# EBF6ULL_B1____AD.net
KiCad netlist of a schematic drawn in Altium Designer
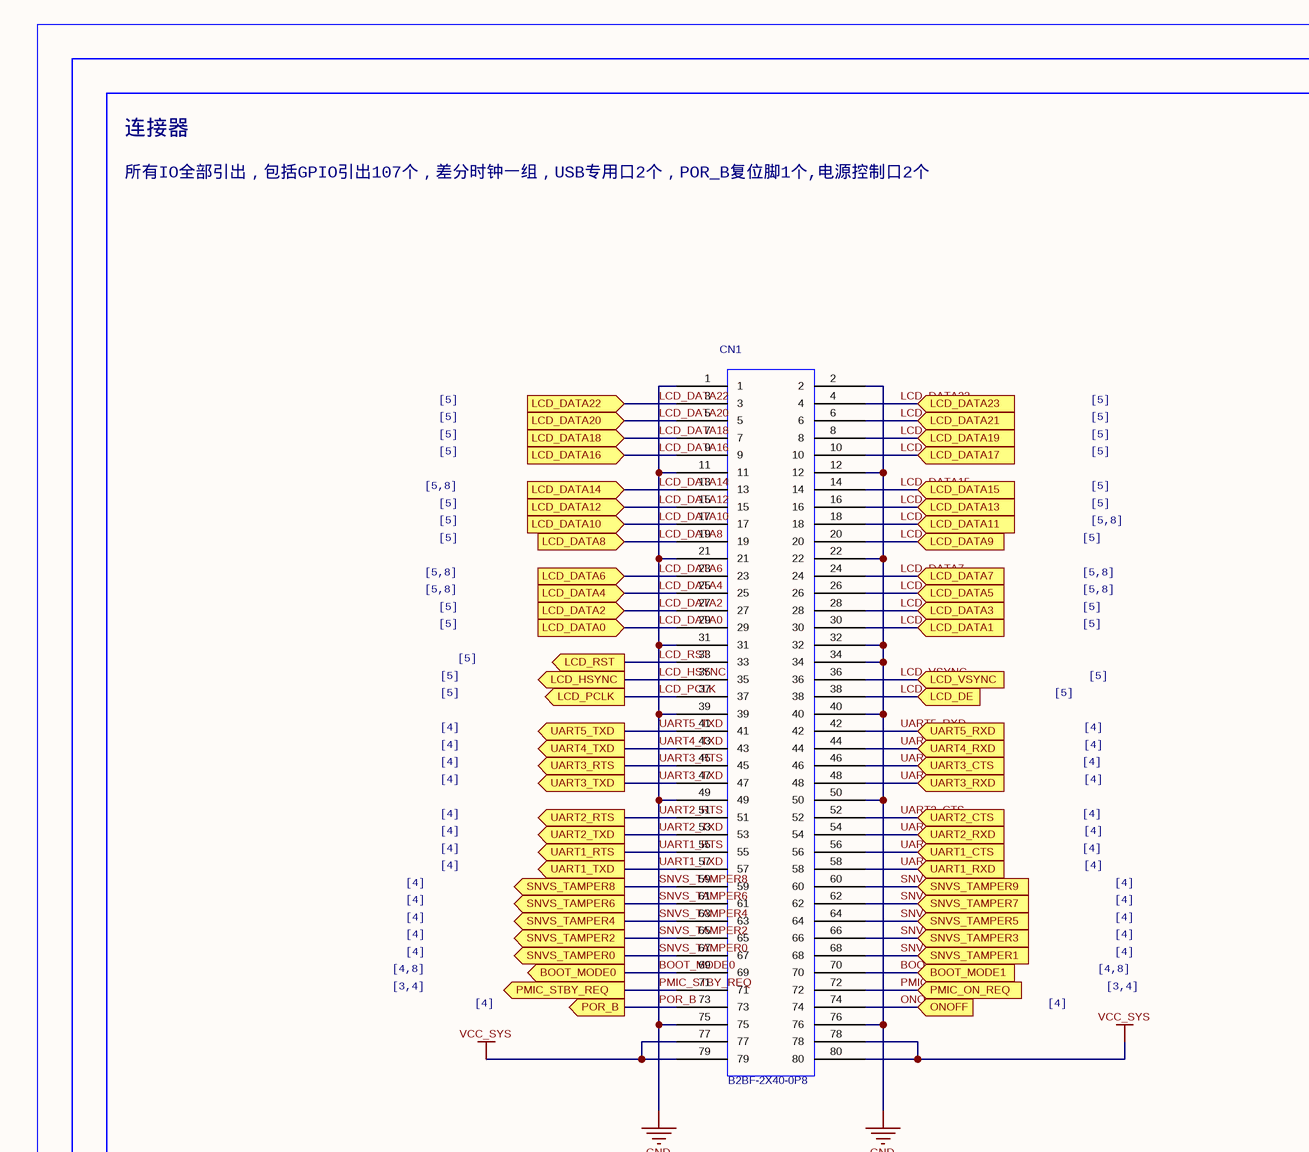
[diagram p0: 野火_EBF6ULL B1 核心板_原理图封装参考设计_AD格式.SchDoc, top left]
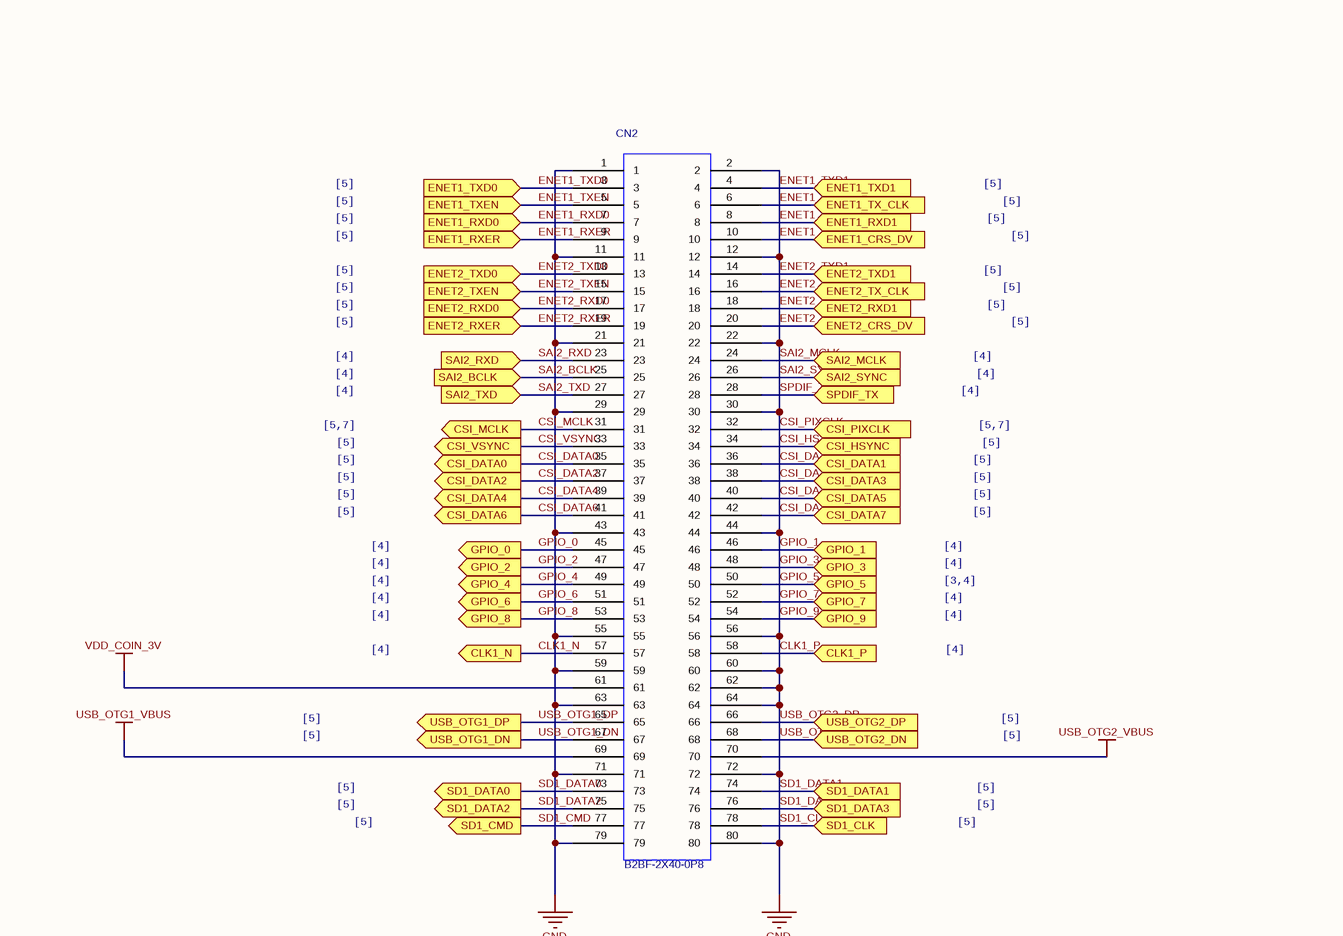
[diagram p1: 野火_EBF6ULL B1 核心板_原理图封装参考设计_AD格式.SchDoc, top right]
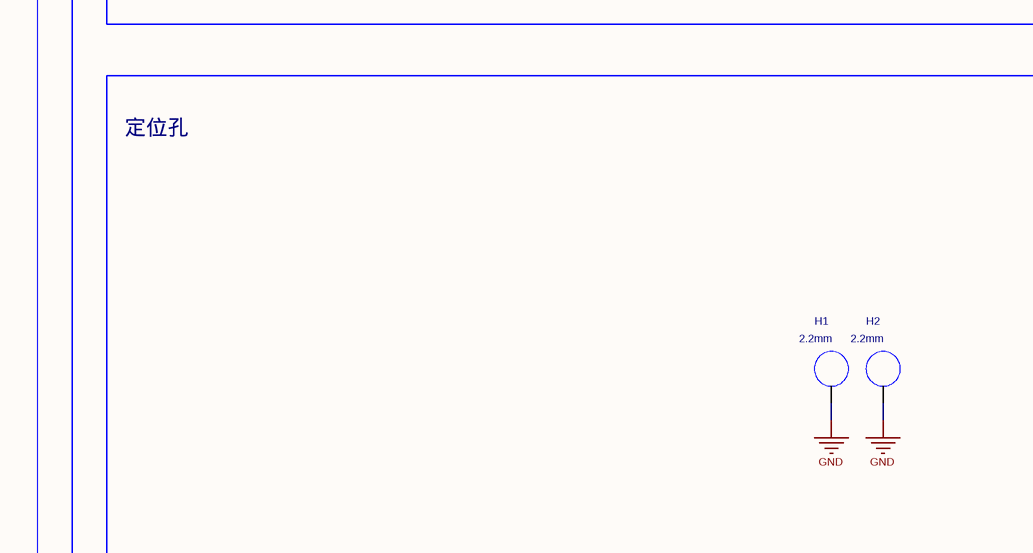
[diagram p2: 野火_EBF6ULL B1 核心板_原理图封装参考设计_AD格式.SchDoc, bottom left]
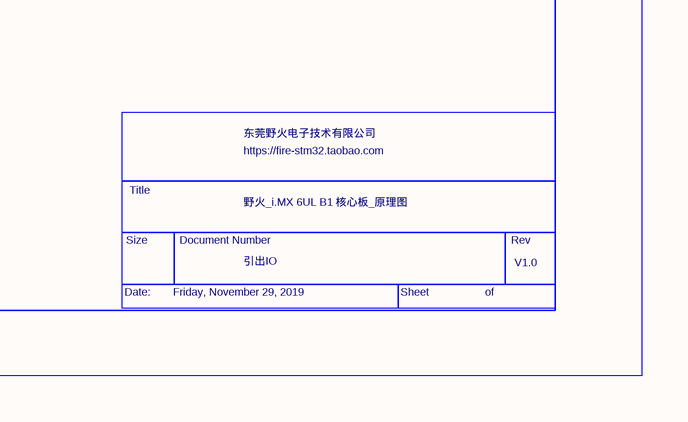
[diagram p3: 野火_EBF6ULL B1 核心板_原理图封装参考设计_AD格式.SchDoc, bottom right]

(export (version "E")
  (design (tool "Eeschema 10.0.6"))
  (components
    (comp (ref "CN1")
      (value "B2BF-2X40-0P8")
      (footprint "B2BF-2X40-0P8")
      (fields (field (name "Comment") "B2BF_2X40_A"))
      (libsource (lib "*") (part "B2BF_2X40_A"))
    )
    (comp (ref "CN2")
      (value "B2BF-2X40-0P8")
      (footprint "B2BF-2X40-0P8")
      (fields (field (name "Comment") "B2BF_2X40_A"))
      (libsource (lib "*") (part "B2BF_2X40_A"))
    )
    (comp (ref "H1")
      (value "2.2mm")
      (footprint "T2_5-4")
      (description "FASTENER, STANDOFF 4.5MMX3.53XM3.0X0.5 ROUND THR .635\"L BRASS")
      (fields (field (name "Comment") "SPACER_0"))
      (libsource (lib "*") (part "SPACER_0"))
    )
    (comp (ref "H2")
      (value "2.2mm")
      (footprint "T2_5-4")
      (description "FASTENER, STANDOFF 4.5MMX3.53XM3.0X0.5 ROUND THR .635\"L BRASS")
      (fields (field (name "Comment") "SPACER_0"))
      (libsource (lib "*") (part "SPACER_0"))
    )
  )
  (nets
    (net (code "1") (name "/BOOT_MODE1") (class "Default")
      (node (ref "CN1") (pin "70") (pinfunction "70_70") (pintype "passive"))
    )
    (net (code "2") (name "/CLK1_N") (class "Default")
      (node (ref "CN2") (pin "57") (pinfunction "57_57") (pintype "passive"))
    )
    (net (code "3") (name "/CSI_DATA0") (class "Default")
      (node (ref "CN2") (pin "35") (pinfunction "35_35") (pintype "passive"))
    )
    (net (code "4") (name "/CSI_DATA2") (class "Default")
      (node (ref "CN2") (pin "37") (pinfunction "37_37") (pintype "passive"))
    )
    (net (code "5") (name "/CSI_DATA4") (class "Default")
      (node (ref "CN2") (pin "39") (pinfunction "39_39") (pintype "passive"))
    )
    (net (code "6") (name "/CSI_DATA6") (class "Default")
      (node (ref "CN2") (pin "41") (pinfunction "41_41") (pintype "passive"))
    )
    (net (code "7") (name "/CSI_MCLK") (class "Default")
      (node (ref "CN2") (pin "31") (pinfunction "31_31") (pintype "passive"))
    )
    (net (code "8") (name "/CSI_VSYNC") (class "Default")
      (node (ref "CN2") (pin "33") (pinfunction "33_33") (pintype "passive"))
    )
    (net (code "9") (name "/ENET1_RXD0") (class "Default")
      (node (ref "CN2") (pin "7") (pinfunction "7_7") (pintype "passive"))
    )
    (net (code "10") (name "/ENET1_RXER") (class "Default")
      (node (ref "CN2") (pin "9") (pinfunction "9_9") (pintype "passive"))
    )
    (net (code "11") (name "/ENET1_TXD0") (class "Default")
      (node (ref "CN2") (pin "3") (pinfunction "3_3") (pintype "passive"))
    )
    (net (code "12") (name "/ENET1_TXEN") (class "Default")
      (node (ref "CN2") (pin "5") (pinfunction "5_5") (pintype "passive"))
    )
    (net (code "13") (name "/ENET2_RXD0") (class "Default")
      (node (ref "CN2") (pin "17") (pinfunction "17_17") (pintype "passive"))
    )
    (net (code "14") (name "/ENET2_RXER") (class "Default")
      (node (ref "CN2") (pin "19") (pinfunction "19_19") (pintype "passive"))
    )
    (net (code "15") (name "/ENET2_TXD0") (class "Default")
      (node (ref "CN2") (pin "13") (pinfunction "13_13") (pintype "passive"))
    )
    (net (code "16") (name "/ENET2_TXEN") (class "Default")
      (node (ref "CN2") (pin "15") (pinfunction "15_15") (pintype "passive"))
    )
    (net (code "17") (name "/GPIO_0") (class "Default")
      (node (ref "CN2") (pin "45") (pinfunction "45_45") (pintype "passive"))
    )
    (net (code "18") (name "/GPIO_2") (class "Default")
      (node (ref "CN2") (pin "47") (pinfunction "47_47") (pintype "passive"))
    )
    (net (code "19") (name "/GPIO_4") (class "Default")
      (node (ref "CN2") (pin "49") (pinfunction "49_49") (pintype "passive"))
    )
    (net (code "20") (name "/GPIO_6") (class "Default")
      (node (ref "CN2") (pin "51") (pinfunction "51_51") (pintype "passive"))
    )
    (net (code "21") (name "/GPIO_8") (class "Default")
      (node (ref "CN2") (pin "53") (pinfunction "53_53") (pintype "passive"))
    )
    (net (code "22") (name "/LCD_DATA1") (class "Default")
      (node (ref "CN1") (pin "30") (pinfunction "30_30") (pintype "passive"))
    )
    (net (code "23") (name "/LCD_DATA3") (class "Default")
      (node (ref "CN1") (pin "28") (pinfunction "28_28") (pintype "passive"))
    )
    (net (code "24") (name "/LCD_DATA5") (class "Default")
      (node (ref "CN1") (pin "26") (pinfunction "26_26") (pintype "passive"))
    )
    (net (code "25") (name "/LCD_DATA7") (class "Default")
      (node (ref "CN1") (pin "24") (pinfunction "24_24") (pintype "passive"))
    )
    (net (code "26") (name "/LCD_DATA9") (class "Default")
      (node (ref "CN1") (pin "20") (pinfunction "20_20") (pintype "passive"))
    )
    (net (code "27") (name "/LCD_DATA11") (class "Default")
      (node (ref "CN1") (pin "18") (pinfunction "18_18") (pintype "passive"))
    )
    (net (code "28") (name "/LCD_DATA13") (class "Default")
      (node (ref "CN1") (pin "16") (pinfunction "16_16") (pintype "passive"))
    )
    (net (code "29") (name "/LCD_DATA15") (class "Default")
      (node (ref "CN1") (pin "14") (pinfunction "14_14") (pintype "passive"))
    )
    (net (code "30") (name "/LCD_DATA17") (class "Default")
      (node (ref "CN1") (pin "10") (pinfunction "10_10") (pintype "passive"))
    )
    (net (code "31") (name "/LCD_DATA19") (class "Default")
      (node (ref "CN1") (pin "8") (pinfunction "8_8") (pintype "passive"))
    )
    (net (code "32") (name "/LCD_DATA21") (class "Default")
      (node (ref "CN1") (pin "6") (pinfunction "6_6") (pintype "passive"))
    )
    (net (code "33") (name "/LCD_DATA23") (class "Default")
      (node (ref "CN1") (pin "4") (pinfunction "4_4") (pintype "passive"))
    )
    (net (code "34") (name "/LCD_DE") (class "Default")
      (node (ref "CN1") (pin "38") (pinfunction "38_38") (pintype "passive"))
    )
    (net (code "35") (name "/LCD_VSYNC") (class "Default")
      (node (ref "CN1") (pin "36") (pinfunction "36_36") (pintype "passive"))
    )
    (net (code "36") (name "/ONOFF") (class "Default")
      (node (ref "CN1") (pin "74") (pinfunction "74_74") (pintype "passive"))
    )
    (net (code "37") (name "/PMIC_ON_REQ") (class "Default")
      (node (ref "CN1") (pin "72") (pinfunction "72_72") (pintype "passive"))
    )
    (net (code "38") (name "/SAI2_BCLK") (class "Default")
      (node (ref "CN2") (pin "25") (pinfunction "25_25") (pintype "passive"))
    )
    (net (code "39") (name "/SAI2_RXD") (class "Default")
      (node (ref "CN2") (pin "23") (pinfunction "23_23") (pintype "passive"))
    )
    (net (code "40") (name "/SAI2_TXD") (class "Default")
      (node (ref "CN2") (pin "27") (pinfunction "27_27") (pintype "passive"))
    )
    (net (code "41") (name "/SD1_CMD") (class "Default")
      (node (ref "CN2") (pin "77") (pinfunction "77_77") (pintype "passive"))
    )
    (net (code "42") (name "/SD1_DATA0") (class "Default")
      (node (ref "CN2") (pin "73") (pinfunction "73_73") (pintype "passive"))
    )
    (net (code "43") (name "/SD1_DATA2") (class "Default")
      (node (ref "CN2") (pin "75") (pinfunction "75_75") (pintype "passive"))
    )
    (net (code "44") (name "/SNVS_TAMPER1") (class "Default")
      (node (ref "CN1") (pin "68") (pinfunction "68_68") (pintype "passive"))
    )
    (net (code "45") (name "/SNVS_TAMPER3") (class "Default")
      (node (ref "CN1") (pin "66") (pinfunction "66_66") (pintype "passive"))
    )
    (net (code "46") (name "/SNVS_TAMPER5") (class "Default")
      (node (ref "CN1") (pin "64") (pinfunction "64_64") (pintype "passive"))
    )
    (net (code "47") (name "/SNVS_TAMPER7") (class "Default")
      (node (ref "CN1") (pin "62") (pinfunction "62_62") (pintype "passive"))
    )
    (net (code "48") (name "/SNVS_TAMPER9") (class "Default")
      (node (ref "CN1") (pin "60") (pinfunction "60_60") (pintype "passive"))
    )
    (net (code "49") (name "/UART1_CTS") (class "Default")
      (node (ref "CN1") (pin "56") (pinfunction "56_56") (pintype "passive"))
    )
    (net (code "50") (name "/UART1_RXD") (class "Default")
      (node (ref "CN1") (pin "58") (pinfunction "58_58") (pintype "passive"))
    )
    (net (code "51") (name "/UART2_CTS") (class "Default")
      (node (ref "CN1") (pin "52") (pinfunction "52_52") (pintype "passive"))
    )
    (net (code "52") (name "/UART2_RXD") (class "Default")
      (node (ref "CN1") (pin "54") (pinfunction "54_54") (pintype "passive"))
    )
    (net (code "53") (name "/UART3_CTS") (class "Default")
      (node (ref "CN1") (pin "46") (pinfunction "46_46") (pintype "passive"))
    )
    (net (code "54") (name "/UART3_RXD") (class "Default")
      (node (ref "CN1") (pin "48") (pinfunction "48_48") (pintype "passive"))
    )
    (net (code "55") (name "/UART4_RXD") (class "Default")
      (node (ref "CN1") (pin "44") (pinfunction "44_44") (pintype "passive"))
    )
    (net (code "56") (name "/UART5_RXD") (class "Default")
      (node (ref "CN1") (pin "42") (pinfunction "42_42") (pintype "passive"))
    )
    (net (code "57") (name "/USB_OTG1_DN") (class "Default")
      (node (ref "CN2") (pin "67") (pinfunction "67_67") (pintype "passive"))
    )
    (net (code "58") (name "/USB_OTG1_DP") (class "Default")
      (node (ref "CN2") (pin "65") (pinfunction "65_65") (pintype "passive"))
    )
    (net (code "59") (name "GND") (class "Default")
      (node (ref "CN1") (pin "1") (pinfunction "1_1") (pintype "passive"))
      (node (ref "CN1") (pin "11") (pinfunction "11_11") (pintype "passive"))
      (node (ref "CN1") (pin "12") (pinfunction "12_12") (pintype "passive"))
      (node (ref "CN1") (pin "13") (pinfunction "13_13") (pintype "passive"))
      (node (ref "CN1") (pin "15") (pinfunction "15_15") (pintype "passive"))
      (node (ref "CN1") (pin "17") (pinfunction "17_17") (pintype "passive"))
      (node (ref "CN1") (pin "19") (pinfunction "19_19") (pintype "passive"))
      (node (ref "CN1") (pin "2") (pinfunction "2_2") (pintype "passive"))
      (node (ref "CN1") (pin "21") (pinfunction "21_21") (pintype "passive"))
      (node (ref "CN1") (pin "22") (pinfunction "22_22") (pintype "passive"))
      (node (ref "CN1") (pin "23") (pinfunction "23_23") (pintype "passive"))
      (node (ref "CN1") (pin "25") (pinfunction "25_25") (pintype "passive"))
      (node (ref "CN1") (pin "27") (pinfunction "27_27") (pintype "passive"))
      (node (ref "CN1") (pin "29") (pinfunction "29_29") (pintype "passive"))
      (node (ref "CN1") (pin "3") (pinfunction "3_3") (pintype "passive"))
      (node (ref "CN1") (pin "31") (pinfunction "31_31") (pintype "passive"))
      (node (ref "CN1") (pin "32") (pinfunction "32_32") (pintype "passive"))
      (node (ref "CN1") (pin "33") (pinfunction "33_33") (pintype "passive"))
      (node (ref "CN1") (pin "34") (pinfunction "34_34") (pintype "passive"))
      (node (ref "CN1") (pin "35") (pinfunction "35_35") (pintype "passive"))
      (node (ref "CN1") (pin "37") (pinfunction "37_37") (pintype "passive"))
      (node (ref "CN1") (pin "39") (pinfunction "39_39") (pintype "passive"))
      (node (ref "CN1") (pin "40") (pinfunction "40_40") (pintype "passive"))
      (node (ref "CN1") (pin "41") (pinfunction "41_41") (pintype "passive"))
      (node (ref "CN1") (pin "43") (pinfunction "43_43") (pintype "passive"))
      (node (ref "CN1") (pin "45") (pinfunction "45_45") (pintype "passive"))
      (node (ref "CN1") (pin "47") (pinfunction "47_47") (pintype "passive"))
      (node (ref "CN1") (pin "49") (pinfunction "49_49") (pintype "passive"))
      (node (ref "CN1") (pin "5") (pinfunction "5_5") (pintype "passive"))
      (node (ref "CN1") (pin "50") (pinfunction "50_50") (pintype "passive"))
      (node (ref "CN1") (pin "51") (pinfunction "51_51") (pintype "passive"))
      (node (ref "CN1") (pin "53") (pinfunction "53_53") (pintype "passive"))
      (node (ref "CN1") (pin "55") (pinfunction "55_55") (pintype "passive"))
      (node (ref "CN1") (pin "57") (pinfunction "57_57") (pintype "passive"))
      (node (ref "CN1") (pin "59") (pinfunction "59_59") (pintype "passive"))
      (node (ref "CN1") (pin "61") (pinfunction "61_61") (pintype "passive"))
      (node (ref "CN1") (pin "63") (pinfunction "63_63") (pintype "passive"))
      (node (ref "CN1") (pin "65") (pinfunction "65_65") (pintype "passive"))
      (node (ref "CN1") (pin "67") (pinfunction "67_67") (pintype "passive"))
      (node (ref "CN1") (pin "69") (pinfunction "69_69") (pintype "passive"))
      (node (ref "CN1") (pin "7") (pinfunction "7_7") (pintype "passive"))
      (node (ref "CN1") (pin "71") (pinfunction "71_71") (pintype "passive"))
      (node (ref "CN1") (pin "73") (pinfunction "73_73") (pintype "passive"))
      (node (ref "CN1") (pin "75") (pinfunction "75_75") (pintype "passive"))
      (node (ref "CN1") (pin "76") (pinfunction "76_76") (pintype "passive"))
      (node (ref "CN1") (pin "9") (pinfunction "9_9") (pintype "passive"))
      (node (ref "CN2") (pin "1") (pinfunction "1_1") (pintype "passive"))
      (node (ref "CN2") (pin "10") (pinfunction "10_10") (pintype "passive"))
      (node (ref "CN2") (pin "11") (pinfunction "11_11") (pintype "passive"))
      (node (ref "CN2") (pin "12") (pinfunction "12_12") (pintype "passive"))
      (node (ref "CN2") (pin "14") (pinfunction "14_14") (pintype "passive"))
      (node (ref "CN2") (pin "16") (pinfunction "16_16") (pintype "passive"))
      (node (ref "CN2") (pin "18") (pinfunction "18_18") (pintype "passive"))
      (node (ref "CN2") (pin "2") (pinfunction "2_2") (pintype "passive"))
      (node (ref "CN2") (pin "20") (pinfunction "20_20") (pintype "passive"))
      (node (ref "CN2") (pin "21") (pinfunction "21_21") (pintype "passive"))
      (node (ref "CN2") (pin "22") (pinfunction "22_22") (pintype "passive"))
      (node (ref "CN2") (pin "24") (pinfunction "24_24") (pintype "passive"))
      (node (ref "CN2") (pin "26") (pinfunction "26_26") (pintype "passive"))
      (node (ref "CN2") (pin "28") (pinfunction "28_28") (pintype "passive"))
      (node (ref "CN2") (pin "29") (pinfunction "29_29") (pintype "passive"))
      (node (ref "CN2") (pin "30") (pinfunction "30_30") (pintype "passive"))
      (node (ref "CN2") (pin "32") (pinfunction "32_32") (pintype "passive"))
      (node (ref "CN2") (pin "34") (pinfunction "34_34") (pintype "passive"))
      (node (ref "CN2") (pin "36") (pinfunction "36_36") (pintype "passive"))
      (node (ref "CN2") (pin "38") (pinfunction "38_38") (pintype "passive"))
      (node (ref "CN2") (pin "4") (pinfunction "4_4") (pintype "passive"))
      (node (ref "CN2") (pin "40") (pinfunction "40_40") (pintype "passive"))
      (node (ref "CN2") (pin "42") (pinfunction "42_42") (pintype "passive"))
      (node (ref "CN2") (pin "43") (pinfunction "43_43") (pintype "passive"))
      (node (ref "CN2") (pin "44") (pinfunction "44_44") (pintype "passive"))
      (node (ref "CN2") (pin "46") (pinfunction "46_46") (pintype "passive"))
      (node (ref "CN2") (pin "48") (pinfunction "48_48") (pintype "passive"))
      (node (ref "CN2") (pin "50") (pinfunction "50_50") (pintype "passive"))
      (node (ref "CN2") (pin "52") (pinfunction "52_52") (pintype "passive"))
      (node (ref "CN2") (pin "54") (pinfunction "54_54") (pintype "passive"))
      (node (ref "CN2") (pin "55") (pinfunction "55_55") (pintype "passive"))
      (node (ref "CN2") (pin "56") (pinfunction "56_56") (pintype "passive"))
      (node (ref "CN2") (pin "58") (pinfunction "58_58") (pintype "passive"))
      (node (ref "CN2") (pin "59") (pinfunction "59_59") (pintype "passive"))
      (node (ref "CN2") (pin "6") (pinfunction "6_6") (pintype "passive"))
      (node (ref "CN2") (pin "60") (pinfunction "60_60") (pintype "passive"))
      (node (ref "CN2") (pin "62") (pinfunction "62_62") (pintype "passive"))
      (node (ref "CN2") (pin "63") (pinfunction "63_63") (pintype "passive"))
      (node (ref "CN2") (pin "64") (pinfunction "64_64") (pintype "passive"))
      (node (ref "CN2") (pin "66") (pinfunction "66_66") (pintype "passive"))
      (node (ref "CN2") (pin "68") (pinfunction "68_68") (pintype "passive"))
      (node (ref "CN2") (pin "71") (pinfunction "71_71") (pintype "passive"))
      (node (ref "CN2") (pin "72") (pinfunction "72_72") (pintype "passive"))
      (node (ref "CN2") (pin "74") (pinfunction "74_74") (pintype "passive"))
      (node (ref "CN2") (pin "76") (pinfunction "76_76") (pintype "passive"))
      (node (ref "CN2") (pin "78") (pinfunction "78_78") (pintype "passive"))
      (node (ref "CN2") (pin "79") (pinfunction "79_79") (pintype "passive"))
      (node (ref "CN2") (pin "8") (pinfunction "8_8") (pintype "passive"))
      (node (ref "CN2") (pin "80") (pinfunction "80_80") (pintype "passive"))
      (node (ref "H1") (pin "1") (pinfunction "NC_1_1") (pintype "passive"))
      (node (ref "H2") (pin "1") (pinfunction "NC_1_1") (pintype "passive"))
    )
    (net (code "60") (name "USB_OTG1_VBUS") (class "Default")
      (node (ref "CN2") (pin "69") (pinfunction "69_69") (pintype "passive"))
    )
    (net (code "61") (name "USB_OTG2_VBUS") (class "Default")
      (node (ref "CN2") (pin "70") (pinfunction "70_70") (pintype "passive"))
    )
    (net (code "62") (name "VCC_SYS") (class "Default")
      (node (ref "CN1") (pin "77") (pinfunction "77_77") (pintype "passive"))
      (node (ref "CN1") (pin "78") (pinfunction "78_78") (pintype "passive"))
      (node (ref "CN1") (pin "79") (pinfunction "79_79") (pintype "passive"))
      (node (ref "CN1") (pin "80") (pinfunction "80_80") (pintype "passive"))
    )
    (net (code "63") (name "VDD_COIN_3V") (class "Default")
      (node (ref "CN2") (pin "61") (pinfunction "61_61") (pintype "passive"))
    )
  )
)
